# bdd_ext_pmm.net
KiCad netlist of a schematic drawn in Altium Designer
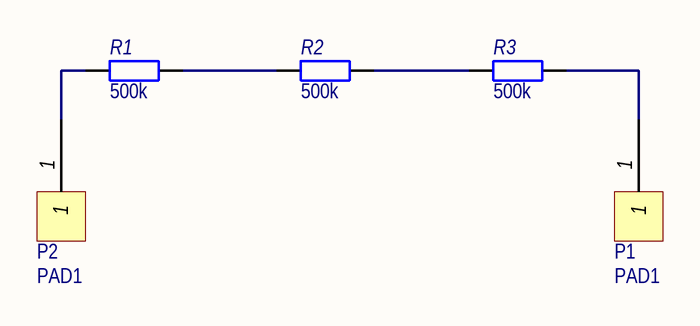
[diagram p0: bdd_ext_pmm.SchDoc]

(export (version "E")
  (design (tool "Eeschema 10.0.6"))
  (components
    (comp (ref "P1") (value "PAD1") (footprint "PAD1") (libsource (lib "PAD1") (part "PAD1")))
    (comp (ref "P2") (value "PAD1") (footprint "PAD1") (libsource (lib "PAD1") (part "PAD1")))
    (comp (ref "R1")
      (value "500k")
      (footprint "SMD_2010_1")
      (description "Resistor")
      (fields (field (name "Comment") "2010"))
      (libsource (lib "Resistor") (part "Resistor"))
    )
    (comp (ref "R2")
      (value "500k")
      (footprint "SMD_2010_1")
      (description "Resistor")
      (fields (field (name "Comment") "2010"))
      (libsource (lib "Resistor") (part "Resistor"))
    )
    (comp (ref "R3")
      (value "500k")
      (footprint "SMD_2010_1")
      (description "Resistor")
      (fields (field (name "Comment") "2010"))
      (libsource (lib "Resistor") (part "Resistor"))
    )
  )
  (nets
    (net (code "1") (name "Net-(P1-Pad1)") (class "Default")
      (node (ref "P1") (pin "1") (pinfunction "1_1") (pintype "passive"))
      (node (ref "R3") (pin "2") (pinfunction "2_2") (pintype "passive"))
    )
    (net (code "2") (name "Net-(P2-Pad1)") (class "Default")
      (node (ref "P2") (pin "1") (pinfunction "1_1") (pintype "passive"))
      (node (ref "R1") (pin "1") (pinfunction "1_1") (pintype "passive"))
    )
    (net (code "3") (name "Net-(R1-Pad2)") (class "Default")
      (node (ref "R1") (pin "2") (pinfunction "2_2") (pintype "passive"))
      (node (ref "R2") (pin "1") (pinfunction "1_1") (pintype "passive"))
    )
    (net (code "4") (name "Net-(R2-Pad2)") (class "Default")
      (node (ref "R2") (pin "2") (pinfunction "2_2") (pintype "passive"))
      (node (ref "R3") (pin "1") (pinfunction "1_1") (pintype "passive"))
    )
  )
)
